# LedController2.net
KiCad netlist of a schematic drawn in EAGLE
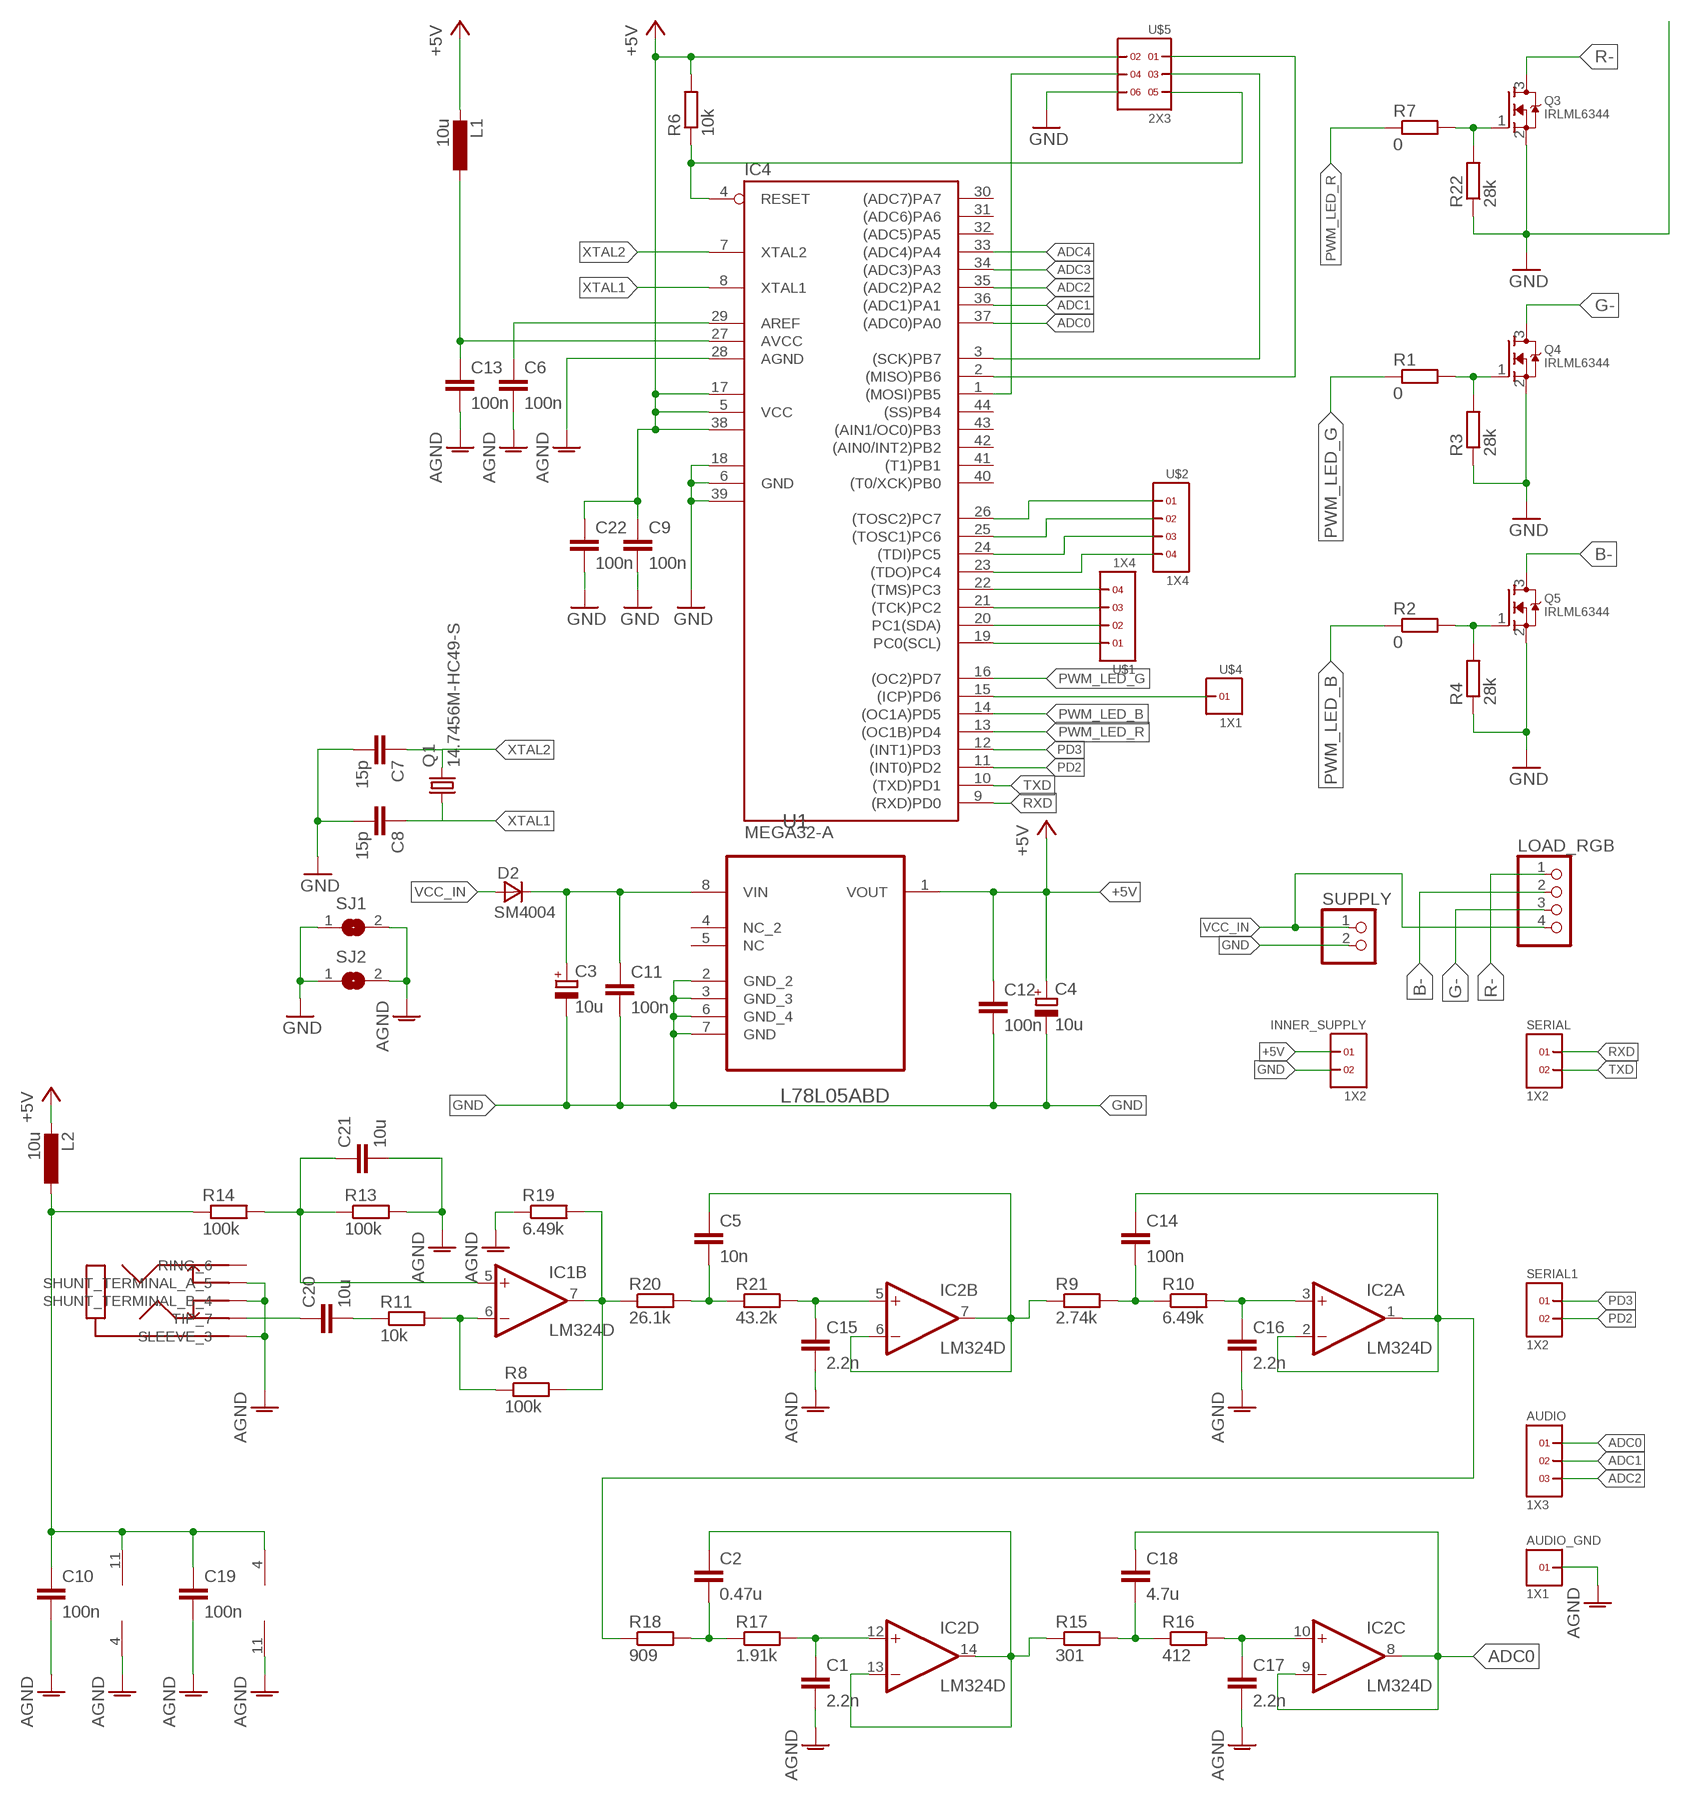
[diagram p0: schematic, sheet 1]

(export (version "E")
  (design (tool "Eeschema 10.0.6"))
  (components
    (comp (ref "AUDIO")
      (value "1X3")
      (footprint "eagle-import:1X3")
      (libsource (lib "eagle-import") (part "1X3"))
    )
    (comp (ref "AUDIO_GND")
      (value "1X1")
      (footprint "eagle-import:1X1")
      (libsource (lib "eagle-import") (part "1X1"))
    )
    (comp (ref "C1")
      (value "2.2n")
      (footprint "eagle-import:C0805")
      (libsource (lib "eagle-import") (part "C-EUC0805"))
    )
    (comp (ref "C2")
      (value "0.47u")
      (footprint "eagle-import:C0805")
      (libsource (lib "eagle-import") (part "C-EUC0805"))
    )
    (comp (ref "C3")
      (value "10u")
      (footprint "eagle-import:SMC_C")
      (libsource (lib "eagle-import") (part "CPOL-EUSMCC"))
    )
    (comp (ref "C4")
      (value "10u")
      (footprint "eagle-import:SMC_C")
      (libsource (lib "eagle-import") (part "CPOL-EUSMCC"))
    )
    (comp (ref "C5")
      (value "10n")
      (footprint "eagle-import:C0805")
      (libsource (lib "eagle-import") (part "C-EUC0805"))
    )
    (comp (ref "C6")
      (value "100n")
      (footprint "eagle-import:C0805")
      (libsource (lib "eagle-import") (part "C-EUC0805"))
    )
    (comp (ref "C7")
      (value "15p")
      (footprint "eagle-import:C0805")
      (libsource (lib "eagle-import") (part "C-EUC0805"))
    )
    (comp (ref "C8")
      (value "15p")
      (footprint "eagle-import:C0805")
      (libsource (lib "eagle-import") (part "C-EUC0805"))
    )
    (comp (ref "C9")
      (value "100n")
      (footprint "eagle-import:C0805")
      (libsource (lib "eagle-import") (part "C-EUC0805"))
    )
    (comp (ref "C10")
      (value "100n")
      (footprint "eagle-import:C0805")
      (libsource (lib "eagle-import") (part "C-EUC0805"))
    )
    (comp (ref "C11")
      (value "100n")
      (footprint "eagle-import:C0805")
      (libsource (lib "eagle-import") (part "C-EUC0805"))
    )
    (comp (ref "C12")
      (value "100n")
      (footprint "eagle-import:C0805")
      (libsource (lib "eagle-import") (part "C-EUC0805"))
    )
    (comp (ref "C13")
      (value "100n")
      (footprint "eagle-import:C0805")
      (libsource (lib "eagle-import") (part "C-EUC0805"))
    )
    (comp (ref "C14")
      (value "100n")
      (footprint "eagle-import:C0805")
      (libsource (lib "eagle-import") (part "C-EUC0805"))
    )
    (comp (ref "C15")
      (value "2.2n")
      (footprint "eagle-import:C0805")
      (libsource (lib "eagle-import") (part "C-EUC0805"))
    )
    (comp (ref "C16")
      (value "2.2n")
      (footprint "eagle-import:C0805")
      (libsource (lib "eagle-import") (part "C-EUC0805"))
    )
    (comp (ref "C17")
      (value "2.2n")
      (footprint "eagle-import:C0805")
      (libsource (lib "eagle-import") (part "C-EUC0805"))
    )
    (comp (ref "C18")
      (value "4.7u")
      (footprint "eagle-import:C0805")
      (libsource (lib "eagle-import") (part "C-EUC0805"))
    )
    (comp (ref "C19")
      (value "100n")
      (footprint "eagle-import:C0805")
      (libsource (lib "eagle-import") (part "C-EUC0805"))
    )
    (comp (ref "C20")
      (value "10u")
      (footprint "eagle-import:C0805")
      (libsource (lib "eagle-import") (part "C-EUC0805"))
    )
    (comp (ref "C21")
      (value "10u")
      (footprint "eagle-import:C0805")
      (libsource (lib "eagle-import") (part "C-EUC0805"))
    )
    (comp (ref "C22")
      (value "100n")
      (footprint "eagle-import:C0805")
      (libsource (lib "eagle-import") (part "C-EUC0805"))
    )
    (comp (ref "D2")
      (value "SM4004")
      (footprint "eagle-import:MELF-MLL41")
      (libsource (lib "eagle-import") (part "SM4004"))
    )
    (comp (ref "IC1")
      (value "LM324D")
      (footprint "eagle-import:SO14")
      (libsource (lib "eagle-import") (part "LM324D"))
    )
    (comp (ref "IC2")
      (value "LM324D")
      (footprint "eagle-import:SO14")
      (libsource (lib "eagle-import") (part "LM324D"))
    )
    (comp (ref "IC4")
      (value "MEGA32-A")
      (footprint "eagle-import:TQFP44")
      (libsource (lib "eagle-import") (part "MEGA32-A"))
    )
    (comp (ref "INNER_SUPPLY")
      (value "1X2")
      (footprint "eagle-import:1X2")
      (libsource (lib "eagle-import") (part "1X2"))
    )
    (comp (ref "L1")
      (value "10u")
      (footprint "eagle-import:L1812")
      (libsource (lib "eagle-import") (part "L-EUL1812"))
    )
    (comp (ref "L2")
      (value "10u")
      (footprint "eagle-import:L1812")
      (libsource (lib "eagle-import") (part "L-EUL1812"))
    )
    (comp (ref "LOAD_RGB")
      (value "PINHD-1X4/90")
      (footprint "eagle-import:1X04_90")
      (libsource (lib "eagle-import") (part "PINHD-1X4/90"))
    )
    (comp (ref "Q1")
      (value "14.7456M-HC49-S")
      (footprint "eagle-import:HC49_S")
      (libsource (lib "eagle-import") (part "CRYSTALHC49S"))
    )
    (comp (ref "Q3")
      (value "IRLML6344")
      (footprint "eagle-import:SOT23")
      (libsource (lib "eagle-import") (part "MOSFET-NREFLOW"))
    )
    (comp (ref "Q4")
      (value "IRLML6344")
      (footprint "eagle-import:SOT23")
      (libsource (lib "eagle-import") (part "MOSFET-NREFLOW"))
    )
    (comp (ref "Q5")
      (value "IRLML6344")
      (footprint "eagle-import:SOT23")
      (libsource (lib "eagle-import") (part "MOSFET-NREFLOW"))
    )
    (comp (ref "R1")
      (value "0")
      (footprint "eagle-import:R0805")
      (libsource (lib "eagle-import") (part "R-EU_R0805"))
    )
    (comp (ref "R2")
      (value "0")
      (footprint "eagle-import:R0805")
      (libsource (lib "eagle-import") (part "R-EU_R0805"))
    )
    (comp (ref "R3")
      (value "28k")
      (footprint "eagle-import:R0805")
      (libsource (lib "eagle-import") (part "R-EU_R0805"))
    )
    (comp (ref "R4")
      (value "28k")
      (footprint "eagle-import:R0805")
      (libsource (lib "eagle-import") (part "R-EU_R0805"))
    )
    (comp (ref "R6")
      (value "10k")
      (footprint "eagle-import:R0805")
      (libsource (lib "eagle-import") (part "R-EU_R0805"))
    )
    (comp (ref "R7")
      (value "0")
      (footprint "eagle-import:R0805")
      (libsource (lib "eagle-import") (part "R-EU_R0805"))
    )
    (comp (ref "R8")
      (value "100k")
      (footprint "eagle-import:R0805")
      (libsource (lib "eagle-import") (part "R-EU_R0805"))
    )
    (comp (ref "R9")
      (value "2.74k")
      (footprint "eagle-import:R0805")
      (libsource (lib "eagle-import") (part "R-EU_R0805"))
    )
    (comp (ref "R10")
      (value "6.49k")
      (footprint "eagle-import:R0805")
      (libsource (lib "eagle-import") (part "R-EU_R0805"))
    )
    (comp (ref "R11")
      (value "10k")
      (footprint "eagle-import:R0805")
      (libsource (lib "eagle-import") (part "R-EU_R0805"))
    )
    (comp (ref "R13")
      (value "100k")
      (footprint "eagle-import:R0805")
      (libsource (lib "eagle-import") (part "R-EU_R0805"))
    )
    (comp (ref "R14")
      (value "100k")
      (footprint "eagle-import:R0805")
      (libsource (lib "eagle-import") (part "R-EU_R0805"))
    )
    (comp (ref "R15")
      (value "301")
      (footprint "eagle-import:R0805")
      (libsource (lib "eagle-import") (part "R-EU_R0805"))
    )
    (comp (ref "R16")
      (value "412")
      (footprint "eagle-import:R0805")
      (libsource (lib "eagle-import") (part "R-EU_R0805"))
    )
    (comp (ref "R17")
      (value "1.91k")
      (footprint "eagle-import:R0805")
      (libsource (lib "eagle-import") (part "R-EU_R0805"))
    )
    (comp (ref "R18")
      (value "909")
      (footprint "eagle-import:R0805")
      (libsource (lib "eagle-import") (part "R-EU_R0805"))
    )
    (comp (ref "R19")
      (value "6.49k")
      (footprint "eagle-import:R0805")
      (libsource (lib "eagle-import") (part "R-EU_R0805"))
    )
    (comp (ref "R20")
      (value "26.1k")
      (footprint "eagle-import:R0805")
      (libsource (lib "eagle-import") (part "R-EU_R0805"))
    )
    (comp (ref "R21")
      (value "43.2k")
      (footprint "eagle-import:R0805")
      (libsource (lib "eagle-import") (part "R-EU_R0805"))
    )
    (comp (ref "R22")
      (value "28k")
      (footprint "eagle-import:R0805")
      (libsource (lib "eagle-import") (part "R-EU_R0805"))
    )
    (comp (ref "SERIAL")
      (value "1X2")
      (footprint "eagle-import:1X2")
      (libsource (lib "eagle-import") (part "1X2"))
    )
    (comp (ref "SERIAL1")
      (value "1X2")
      (footprint "eagle-import:1X2")
      (libsource (lib "eagle-import") (part "1X2"))
    )
    (comp (ref "SJ1") (value "SJ") (footprint "eagle-import:SJ") (libsource (lib "eagle-import") (part "SJ")))
    (comp (ref "SJ2") (value "SJ") (footprint "eagle-import:SJ") (libsource (lib "eagle-import") (part "SJ")))
    (comp (ref "SUPPLY")
      (value "PINHD-1X2/90")
      (footprint "eagle-import:1X02_90")
      (libsource (lib "eagle-import") (part "PINHD-1X2/90"))
    )
    (comp (ref "U$1")
      (value "1X4")
      (footprint "eagle-import:1X4")
      (libsource (lib "eagle-import") (part "1X4"))
    )
    (comp (ref "U$2")
      (value "1X4")
      (footprint "eagle-import:1X4")
      (libsource (lib "eagle-import") (part "1X4"))
    )
    (comp (ref "U$4")
      (value "1X1")
      (footprint "eagle-import:1X1")
      (libsource (lib "eagle-import") (part "1X1"))
    )
    (comp (ref "U$5")
      (value "2X3")
      (footprint "eagle-import:2X3")
      (libsource (lib "eagle-import") (part "2X3"))
    )
    (comp (ref "U$6")
      (value "JACK35")
      (footprint "eagle-import:JACK35")
      (libsource (lib "eagle-import") (part "JACK35"))
    )
    (comp (ref "U1")
      (value "L78L05ABD")
      (footprint "eagle-import:SOIC127P600X175-8N")
      (libsource (lib "eagle-import") (part "L78L05ABD"))
    )
  )
  (nets
    (net (code "1") (name "+5V") (class "Default")
      (node (ref "C12") (pin "1") (pinfunction "1_1") (pintype "passive"))
      (node (ref "C22") (pin "1") (pinfunction "1_1") (pintype "passive"))
      (node (ref "C4") (pin "+") (pinfunction "+_+") (pintype "passive"))
      (node (ref "C9") (pin "1") (pinfunction "1_1") (pintype "passive"))
      (node (ref "IC4") (pin "17") (pinfunction "VCC1_17") (pintype "power_in"))
      (node (ref "IC4") (pin "38") (pinfunction "VCC2_38") (pintype "power_in"))
      (node (ref "IC4") (pin "5") (pinfunction "VCC_5") (pintype "power_in"))
      (node (ref "INNER_SUPPLY") (pin "1") (pinfunction "1_1") (pintype "bidirectional"))
      (node (ref "L1") (pin "2") (pinfunction "2_2") (pintype "passive"))
      (node (ref "L2") (pin "2") (pinfunction "2_2") (pintype "passive"))
      (node (ref "R6") (pin "2") (pinfunction "2_2") (pintype "passive"))
      (node (ref "U$5") (pin "2") (pinfunction "2_2") (pintype "bidirectional"))
      (node (ref "U1") (pin "1") (pinfunction "VOUT_1") (pintype "output"))
    )
    (net (code "2") (name "ADC0") (class "Default")
      (node (ref "AUDIO") (pin "1") (pinfunction "1_1") (pintype "bidirectional"))
      (node (ref "C18") (pin "1") (pinfunction "1_1") (pintype "passive"))
      (node (ref "IC2") (pin "8") (pinfunction "OUT_8") (pintype "output"))
      (node (ref "IC2") (pin "9") (pinfunction "-IN_9") (pintype "input"))
      (node (ref "IC4") (pin "37") (pinfunction "(ADC0)PA0_37") (pintype "bidirectional"))
    )
    (net (code "3") (name "ADC1") (class "Default")
      (node (ref "AUDIO") (pin "2") (pinfunction "2_2") (pintype "bidirectional"))
      (node (ref "IC4") (pin "36") (pinfunction "(ADC1)PA1_36") (pintype "bidirectional"))
    )
    (net (code "4") (name "ADC2") (class "Default")
      (node (ref "AUDIO") (pin "3") (pinfunction "3_3") (pintype "bidirectional"))
      (node (ref "IC4") (pin "35") (pinfunction "(ADC2)PA2_35") (pintype "bidirectional"))
    )
    (net (code "5") (name "ADC3") (class "Default")
      (node (ref "IC4") (pin "34") (pinfunction "(ADC3)PA3_34") (pintype "bidirectional"))
    )
    (net (code "6") (name "ADC4") (class "Default")
      (node (ref "IC4") (pin "33") (pinfunction "(ADC4)PA4_33") (pintype "bidirectional"))
    )
    (net (code "7") (name "AGND") (class "Default")
      (node (ref "AUDIO_GND") (pin "1") (pinfunction "1_1") (pintype "bidirectional"))
      (node (ref "C1") (pin "2") (pinfunction "2_2") (pintype "passive"))
      (node (ref "C10") (pin "2") (pinfunction "2_2") (pintype "passive"))
      (node (ref "C13") (pin "2") (pinfunction "2_2") (pintype "passive"))
      (node (ref "C15") (pin "2") (pinfunction "2_2") (pintype "passive"))
      (node (ref "C16") (pin "2") (pinfunction "2_2") (pintype "passive"))
      (node (ref "C17") (pin "2") (pinfunction "2_2") (pintype "passive"))
      (node (ref "C19") (pin "2") (pinfunction "2_2") (pintype "passive"))
      (node (ref "C21") (pin "2") (pinfunction "2_2") (pintype "passive"))
      (node (ref "C6") (pin "2") (pinfunction "2_2") (pintype "passive"))
      (node (ref "IC1") (pin "11") (pinfunction "V-_11") (pintype "power_in"))
      (node (ref "IC2") (pin "4") (pinfunction "V+_4") (pintype "power_in"))
      (node (ref "IC4") (pin "28") (pinfunction "AGND_28") (pintype "power_in"))
      (node (ref "R13") (pin "2") (pinfunction "2_2") (pintype "passive"))
      (node (ref "R19") (pin "1") (pinfunction "1_1") (pintype "passive"))
      (node (ref "SJ1") (pin "2") (pinfunction "2_2") (pintype "passive"))
      (node (ref "SJ2") (pin "2") (pinfunction "2_2") (pintype "passive"))
      (node (ref "U$6") (pin "SHUNT_TERMINAL_A_5") (pinfunction "SHUNT_TERMINAL_A_5_SHUNT_TERMINAL_A_5") (pintype "bidirectional"))
      (node (ref "U$6") (pin "SHUNT_TERMINAL_B_4") (pinfunction "SHUNT_TERMINAL_B_4_SHUNT_TERMINAL_B_4") (pintype "bidirectional"))
      (node (ref "U$6") (pin "SLEEVE_3") (pinfunction "SLEEVE_3_SLEEVE_3") (pintype "bidirectional"))
    )
    (net (code "8") (name "B-") (class "Default")
      (node (ref "LOAD_RGB") (pin "2") (pinfunction "2_2") (pintype "passive"))
      (node (ref "Q5") (pin "3") (pinfunction "D_3") (pintype "bidirectional"))
    )
    (net (code "9") (name "G-") (class "Default")
      (node (ref "LOAD_RGB") (pin "3") (pinfunction "3_3") (pintype "passive"))
      (node (ref "Q4") (pin "3") (pinfunction "D_3") (pintype "bidirectional"))
    )
    (net (code "10") (name "GND") (class "Default")
      (node (ref "C11") (pin "2") (pinfunction "2_2") (pintype "passive"))
      (node (ref "C12") (pin "2") (pinfunction "2_2") (pintype "passive"))
      (node (ref "C22") (pin "2") (pinfunction "2_2") (pintype "passive"))
      (node (ref "C3") (pin "-") (pinfunction "-_-") (pintype "passive"))
      (node (ref "C4") (pin "-") (pinfunction "-_-") (pintype "passive"))
      (node (ref "C7") (pin "2") (pinfunction "2_2") (pintype "passive"))
      (node (ref "C8") (pin "2") (pinfunction "2_2") (pintype "passive"))
      (node (ref "C9") (pin "2") (pinfunction "2_2") (pintype "passive"))
      (node (ref "IC4") (pin "18") (pinfunction "GND1_18") (pintype "power_in"))
      (node (ref "IC4") (pin "39") (pinfunction "GND2_39") (pintype "power_in"))
      (node (ref "IC4") (pin "6") (pinfunction "GND_6") (pintype "power_in"))
      (node (ref "INNER_SUPPLY") (pin "2") (pinfunction "2_2") (pintype "bidirectional"))
      (node (ref "Q3") (pin "2") (pinfunction "S_2") (pintype "bidirectional"))
      (node (ref "Q4") (pin "2") (pinfunction "S_2") (pintype "bidirectional"))
      (node (ref "Q5") (pin "2") (pinfunction "S_2") (pintype "bidirectional"))
      (node (ref "R22") (pin "1") (pinfunction "1_1") (pintype "passive"))
      (node (ref "R3") (pin "1") (pinfunction "1_1") (pintype "passive"))
      (node (ref "R4") (pin "1") (pinfunction "1_1") (pintype "passive"))
      (node (ref "SJ1") (pin "1") (pinfunction "1_1") (pintype "passive"))
      (node (ref "SJ2") (pin "1") (pinfunction "1_1") (pintype "passive"))
      (node (ref "SUPPLY") (pin "2") (pinfunction "2_2") (pintype "passive"))
      (node (ref "U$5") (pin "6") (pinfunction "6_6") (pintype "bidirectional"))
      (node (ref "U1") (pin "2") (pinfunction "GND_2_2") (pintype "passive"))
      (node (ref "U1") (pin "3") (pinfunction "GND_3_3") (pintype "passive"))
      (node (ref "U1") (pin "6") (pinfunction "GND_4_6") (pintype "passive"))
      (node (ref "U1") (pin "7") (pinfunction "GND_7") (pintype "passive"))
    )
    (net (code "11") (name "Net-(C2-Pad2)") (class "Default")
      (node (ref "C2") (pin "2") (pinfunction "2_2") (pintype "passive"))
      (node (ref "R17") (pin "1") (pinfunction "1_1") (pintype "passive"))
      (node (ref "R18") (pin "2") (pinfunction "2_2") (pintype "passive"))
    )
    (net (code "12") (name "Net-(C5-Pad2)") (class "Default")
      (node (ref "C5") (pin "2") (pinfunction "2_2") (pintype "passive"))
      (node (ref "R20") (pin "2") (pinfunction "2_2") (pintype "passive"))
      (node (ref "R21") (pin "1") (pinfunction "1_1") (pintype "passive"))
    )
    (net (code "13") (name "Net-(C14-Pad2)") (class "Default")
      (node (ref "C14") (pin "2") (pinfunction "2_2") (pintype "passive"))
      (node (ref "R10") (pin "1") (pinfunction "1_1") (pintype "passive"))
      (node (ref "R9") (pin "2") (pinfunction "2_2") (pintype "passive"))
    )
    (net (code "14") (name "Net-(C18-Pad2)") (class "Default")
      (node (ref "C18") (pin "2") (pinfunction "2_2") (pintype "passive"))
      (node (ref "R15") (pin "2") (pinfunction "2_2") (pintype "passive"))
      (node (ref "R16") (pin "1") (pinfunction "1_1") (pintype "passive"))
    )
    (net (code "15") (name "Net-(C20-Pad1)") (class "Default")
      (node (ref "C20") (pin "1") (pinfunction "1_1") (pintype "passive"))
      (node (ref "U$6") (pin "TIP_7") (pinfunction "TIP_7_TIP_7") (pintype "bidirectional"))
    )
    (net (code "16") (name "Net-(C20-Pad2)") (class "Default")
      (node (ref "C20") (pin "2") (pinfunction "2_2") (pintype "passive"))
      (node (ref "R11") (pin "1") (pinfunction "1_1") (pintype "passive"))
    )
    (net (code "17") (name "Net-(IC1B-+IN)") (class "Default")
      (node (ref "C21") (pin "1") (pinfunction "1_1") (pintype "passive"))
      (node (ref "IC1") (pin "5") (pinfunction "+IN_5") (pintype "input"))
      (node (ref "R13") (pin "1") (pinfunction "1_1") (pintype "passive"))
      (node (ref "R14") (pin "2") (pinfunction "2_2") (pintype "passive"))
    )
    (net (code "18") (name "Net-(IC1B--IN)") (class "Default")
      (node (ref "IC1") (pin "6") (pinfunction "-IN_6") (pintype "input"))
      (node (ref "R11") (pin "2") (pinfunction "2_2") (pintype "passive"))
      (node (ref "R8") (pin "1") (pinfunction "1_1") (pintype "passive"))
    )
    (net (code "19") (name "Net-(IC1B-OUT)") (class "Default")
      (node (ref "IC1") (pin "7") (pinfunction "OUT_7") (pintype "output"))
      (node (ref "R19") (pin "2") (pinfunction "2_2") (pintype "passive"))
      (node (ref "R20") (pin "1") (pinfunction "1_1") (pintype "passive"))
      (node (ref "R8") (pin "2") (pinfunction "2_2") (pintype "passive"))
    )
    (net (code "20") (name "Net-(IC1E-V+)") (class "Default")
      (node (ref "C10") (pin "1") (pinfunction "1_1") (pintype "passive"))
      (node (ref "C19") (pin "1") (pinfunction "1_1") (pintype "passive"))
      (node (ref "IC1") (pin "4") (pinfunction "V+_4") (pintype "power_in"))
      (node (ref "IC2") (pin "11") (pinfunction "V-_11") (pintype "power_in"))
      (node (ref "L2") (pin "1") (pinfunction "1_1") (pintype "passive"))
      (node (ref "R14") (pin "1") (pinfunction "1_1") (pintype "passive"))
    )
    (net (code "21") (name "Net-(IC2A-+IN)") (class "Default")
      (node (ref "C16") (pin "1") (pinfunction "1_1") (pintype "passive"))
      (node (ref "IC2") (pin "3") (pinfunction "+IN_3") (pintype "input"))
      (node (ref "R10") (pin "2") (pinfunction "2_2") (pintype "passive"))
    )
    (net (code "22") (name "Net-(IC2A--IN)") (class "Default")
      (node (ref "C14") (pin "1") (pinfunction "1_1") (pintype "passive"))
      (node (ref "IC2") (pin "1") (pinfunction "OUT_1") (pintype "output"))
      (node (ref "IC2") (pin "2") (pinfunction "-IN_2") (pintype "input"))
      (node (ref "R18") (pin "1") (pinfunction "1_1") (pintype "passive"))
    )
    (net (code "23") (name "Net-(IC2B-+IN)") (class "Default")
      (node (ref "C15") (pin "1") (pinfunction "1_1") (pintype "passive"))
      (node (ref "IC2") (pin "5") (pinfunction "+IN_5") (pintype "input"))
      (node (ref "R21") (pin "2") (pinfunction "2_2") (pintype "passive"))
    )
    (net (code "24") (name "Net-(IC2B--IN)") (class "Default")
      (node (ref "C5") (pin "1") (pinfunction "1_1") (pintype "passive"))
      (node (ref "IC2") (pin "6") (pinfunction "-IN_6") (pintype "input"))
      (node (ref "IC2") (pin "7") (pinfunction "OUT_7") (pintype "output"))
      (node (ref "R9") (pin "1") (pinfunction "1_1") (pintype "passive"))
    )
    (net (code "25") (name "Net-(IC2C-+IN)") (class "Default")
      (node (ref "C17") (pin "1") (pinfunction "1_1") (pintype "passive"))
      (node (ref "IC2") (pin "10") (pinfunction "+IN_10") (pintype "input"))
      (node (ref "R16") (pin "2") (pinfunction "2_2") (pintype "passive"))
    )
    (net (code "26") (name "Net-(IC2D-+IN)") (class "Default")
      (node (ref "C1") (pin "1") (pinfunction "1_1") (pintype "passive"))
      (node (ref "IC2") (pin "12") (pinfunction "+IN_12") (pintype "input"))
      (node (ref "R17") (pin "2") (pinfunction "2_2") (pintype "passive"))
    )
    (net (code "27") (name "Net-(IC2D--IN)") (class "Default")
      (node (ref "C2") (pin "1") (pinfunction "1_1") (pintype "passive"))
      (node (ref "IC2") (pin "13") (pinfunction "-IN_13") (pintype "input"))
      (node (ref "IC2") (pin "14") (pinfunction "OUT_14") (pintype "output"))
      (node (ref "R15") (pin "1") (pinfunction "1_1") (pintype "passive"))
    )
    (net (code "28") (name "Net-(IC4-(ICP)PD6)") (class "Default")
      (node (ref "IC4") (pin "15") (pinfunction "(ICP)PD6_15") (pintype "bidirectional"))
      (node (ref "U$4") (pin "1") (pinfunction "1_1") (pintype "bidirectional"))
    )
    (net (code "29") (name "Net-(IC4-(MISO)PB6)") (class "Default")
      (node (ref "IC4") (pin "2") (pinfunction "(MISO)PB6_2") (pintype "bidirectional"))
      (node (ref "U$5") (pin "1") (pinfunction "1_1") (pintype "bidirectional"))
    )
    (net (code "30") (name "Net-(IC4-(MOSI)PB5)") (class "Default")
      (node (ref "IC4") (pin "1") (pinfunction "(MOSI)PB5_1") (pintype "bidirectional"))
      (node (ref "U$5") (pin "4") (pinfunction "4_4") (pintype "bidirectional"))
    )
    (net (code "31") (name "Net-(IC4-(SCK)PB7)") (class "Default")
      (node (ref "IC4") (pin "3") (pinfunction "(SCK)PB7_3") (pintype "bidirectional"))
      (node (ref "U$5") (pin "3") (pinfunction "3_3") (pintype "bidirectional"))
    )
    (net (code "32") (name "Net-(IC4-(TCK)PC2)") (class "Default")
      (node (ref "IC4") (pin "21") (pinfunction "(TCK)PC2_21") (pintype "bidirectional"))
      (node (ref "U$1") (pin "3") (pinfunction "3_3") (pintype "bidirectional"))
    )
    (net (code "33") (name "Net-(IC4-(TDI)PC5)") (class "Default")
      (node (ref "IC4") (pin "24") (pinfunction "(TDI)PC5_24") (pintype "bidirectional"))
      (node (ref "U$2") (pin "3") (pinfunction "3_3") (pintype "bidirectional"))
    )
    (net (code "34") (name "Net-(IC4-(TDO)PC4)") (class "Default")
      (node (ref "IC4") (pin "23") (pinfunction "(TDO)PC4_23") (pintype "bidirectional"))
      (node (ref "U$2") (pin "4") (pinfunction "4_4") (pintype "bidirectional"))
    )
    (net (code "35") (name "Net-(IC4-(TMS)PC3)") (class "Default")
      (node (ref "IC4") (pin "22") (pinfunction "(TMS)PC3_22") (pintype "bidirectional"))
      (node (ref "U$1") (pin "4") (pinfunction "4_4") (pintype "bidirectional"))
    )
    (net (code "36") (name "Net-(IC4-(TOSC1)PC6)") (class "Default")
      (node (ref "IC4") (pin "25") (pinfunction "(TOSC1)PC6_25") (pintype "bidirectional"))
      (node (ref "U$2") (pin "2") (pinfunction "2_2") (pintype "bidirectional"))
    )
    (net (code "37") (name "Net-(IC4-(TOSC2)PC7)") (class "Default")
      (node (ref "IC4") (pin "26") (pinfunction "(TOSC2)PC7_26") (pintype "bidirectional"))
      (node (ref "U$2") (pin "1") (pinfunction "1_1") (pintype "bidirectional"))
    )
    (net (code "38") (name "Net-(IC4-AREF)") (class "Default")
      (node (ref "C6") (pin "1") (pinfunction "1_1") (pintype "passive"))
      (node (ref "IC4") (pin "29") (pinfunction "AREF_29") (pintype "power_in"))
    )
    (net (code "39") (name "Net-(IC4-AVCC)") (class "Default")
      (node (ref "C13") (pin "1") (pinfunction "1_1") (pintype "passive"))
      (node (ref "IC4") (pin "27") (pinfunction "AVCC_27") (pintype "power_in"))
      (node (ref "L1") (pin "1") (pinfunction "1_1") (pintype "passive"))
    )
    (net (code "40") (name "Net-(IC4-PC0(SCL))") (class "Default")
      (node (ref "IC4") (pin "19") (pinfunction "PC0(SCL)_19") (pintype "bidirectional"))
      (node (ref "U$1") (pin "1") (pinfunction "1_1") (pintype "bidirectional"))
    )
    (net (code "41") (name "Net-(IC4-PC1(SDA))") (class "Default")
      (node (ref "IC4") (pin "20") (pinfunction "PC1(SDA)_20") (pintype "bidirectional"))
      (node (ref "U$1") (pin "2") (pinfunction "2_2") (pintype "bidirectional"))
    )
    (net (code "42") (name "Net-(IC4-RESET)") (class "Default")
      (node (ref "IC4") (pin "4") (pinfunction "RESET_4") (pintype "input"))
      (node (ref "R6") (pin "1") (pinfunction "1_1") (pintype "passive"))
      (node (ref "U$5") (pin "5") (pinfunction "5_5") (pintype "bidirectional"))
    )
    (net (code "43") (name "Net-(Q3-G)") (class "Default")
      (node (ref "Q3") (pin "1") (pinfunction "G_1") (pintype "bidirectional"))
      (node (ref "R22") (pin "2") (pinfunction "2_2") (pintype "passive"))
      (node (ref "R7") (pin "2") (pinfunction "2_2") (pintype "passive"))
    )
    (net (code "44") (name "Net-(Q4-G)") (class "Default")
      (node (ref "Q4") (pin "1") (pinfunction "G_1") (pintype "bidirectional"))
      (node (ref "R1") (pin "2") (pinfunction "2_2") (pintype "passive"))
      (node (ref "R3") (pin "2") (pinfunction "2_2") (pintype "passive"))
    )
    (net (code "45") (name "Net-(Q5-G)") (class "Default")
      (node (ref "Q5") (pin "1") (pinfunction "G_1") (pintype "bidirectional"))
      (node (ref "R2") (pin "2") (pinfunction "2_2") (pintype "passive"))
      (node (ref "R4") (pin "2") (pinfunction "2_2") (pintype "passive"))
    )
    (net (code "46") (name "Net-(U1-VIN)") (class "Default")
      (node (ref "C11") (pin "1") (pinfunction "1_1") (pintype "passive"))
      (node (ref "C3") (pin "+") (pinfunction "+_+") (pintype "passive"))
      (node (ref "D2") (pin "C") (pinfunction "C_C") (pintype "passive"))
      (node (ref "U1") (pin "8") (pinfunction "VIN_8") (pintype "power_in"))
    )
    (net (code "47") (name "PD2") (class "Default")
      (node (ref "IC4") (pin "11") (pinfunction "(INT0)PD2_11") (pintype "bidirectional"))
      (node (ref "SERIAL1") (pin "2") (pinfunction "2_2") (pintype "bidirectional"))
    )
    (net (code "48") (name "PD3") (class "Default")
      (node (ref "IC4") (pin "12") (pinfunction "(INT1)PD3_12") (pintype "bidirectional"))
      (node (ref "SERIAL1") (pin "1") (pinfunction "1_1") (pintype "bidirectional"))
    )
    (net (code "49") (name "PWM_LED_B") (class "Default")
      (node (ref "IC4") (pin "14") (pinfunction "(OC1A)PD5_14") (pintype "bidirectional"))
      (node (ref "R2") (pin "1") (pinfunction "1_1") (pintype "passive"))
    )
    (net (code "50") (name "PWM_LED_G") (class "Default")
      (node (ref "IC4") (pin "16") (pinfunction "(OC2)PD7_16") (pintype "bidirectional"))
      (node (ref "R1") (pin "1") (pinfunction "1_1") (pintype "passive"))
    )
    (net (code "51") (name "PWM_LED_R") (class "Default")
      (node (ref "IC4") (pin "13") (pinfunction "(OC1B)PD4_13") (pintype "bidirectional"))
      (node (ref "R7") (pin "1") (pinfunction "1_1") (pintype "passive"))
    )
    (net (code "52") (name "R-") (class "Default")
      (node (ref "LOAD_RGB") (pin "1") (pinfunction "1_1") (pintype "passive"))
      (node (ref "Q3") (pin "3") (pinfunction "D_3") (pintype "bidirectional"))
    )
    (net (code "53") (name "RXD") (class "Default")
      (node (ref "IC4") (pin "9") (pinfunction "(RXD)PD0_9") (pintype "bidirectional"))
      (node (ref "SERIAL") (pin "1") (pinfunction "1_1") (pintype "bidirectional"))
    )
    (net (code "54") (name "TXD") (class "Default")
      (node (ref "IC4") (pin "10") (pinfunction "(TXD)PD1_10") (pintype "bidirectional"))
      (node (ref "SERIAL") (pin "2") (pinfunction "2_2") (pintype "bidirectional"))
    )
    (net (code "55") (name "VCC_IN") (class "Default")
      (node (ref "D2") (pin "A") (pinfunction "A_A") (pintype "passive"))
      (node (ref "LOAD_RGB") (pin "4") (pinfunction "4_4") (pintype "passive"))
      (node (ref "SUPPLY") (pin "1") (pinfunction "1_1") (pintype "passive"))
    )
    (net (code "56") (name "XTAL1") (class "Default")
      (node (ref "C8") (pin "1") (pinfunction "1_1") (pintype "passive"))
      (node (ref "IC4") (pin "8") (pinfunction "XTAL1_8") (pintype "bidirectional"))
      (node (ref "Q1") (pin "1") (pinfunction "1_1") (pintype "passive"))
    )
    (net (code "57") (name "XTAL2") (class "Default")
      (node (ref "C7") (pin "1") (pinfunction "1_1") (pintype "passive"))
      (node (ref "IC4") (pin "7") (pinfunction "XTAL2_7") (pintype "bidirectional"))
      (node (ref "Q1") (pin "2") (pinfunction "2_2") (pintype "passive"))
    )
    (net (code "58") (name "unconnected-(IC4-(ADC5)PA5-Pad32)") (class "Default")
      (node (ref "IC4") (pin "32") (pinfunction "(ADC5)PA5_32") (pintype "bidirectional"))
    )
    (net (code "59") (name "unconnected-(IC4-(ADC6)PA6-Pad31)") (class "Default")
      (node (ref "IC4") (pin "31") (pinfunction "(ADC6)PA6_31") (pintype "bidirectional"))
    )
    (net (code "60") (name "unconnected-(IC4-(ADC7)PA7-Pad30)") (class "Default")
      (node (ref "IC4") (pin "30") (pinfunction "(ADC7)PA7_30") (pintype "bidirectional"))
    )
    (net (code "61") (name "unconnected-(IC4-(AIN0{slash}INT2)PB2-Pad42)") (class "Default")
      (node (ref "IC4") (pin "42") (pinfunction "(AIN0/INT2)PB2_42") (pintype "bidirectional"))
    )
    (net (code "62") (name "unconnected-(IC4-(AIN1{slash}OC0)PB3-Pad43)") (class "Default")
      (node (ref "IC4") (pin "43") (pinfunction "(AIN1/OC0)PB3_43") (pintype "bidirectional"))
    )
    (net (code "63") (name "unconnected-(IC4-(SS)PB4-Pad44)") (class "Default")
      (node (ref "IC4") (pin "44") (pinfunction "(SS)PB4_44") (pintype "bidirectional"))
    )
    (net (code "64") (name "unconnected-(IC4-(T0{slash}XCK)PB0-Pad40)") (class "Default")
      (node (ref "IC4") (pin "40") (pinfunction "(T0/XCK)PB0_40") (pintype "bidirectional"))
    )
    (net (code "65") (name "unconnected-(IC4-(T1)PB1-Pad41)") (class "Default")
      (node (ref "IC4") (pin "41") (pinfunction "(T1)PB1_41") (pintype "bidirectional"))
    )
    (net (code "66") (name "unconnected-(U$6-PadRING_6)") (class "Default")
      (node (ref "U$6") (pin "RING_6") (pinfunction "RING_6_RING_6") (pintype "bidirectional"))
    )
    (net (code "67") (name "unconnected-(U1-NC-Pad5)") (class "Default")
      (node (ref "U1") (pin "5") (pinfunction "NC_5") (pintype "no_connect"))
    )
    (net (code "68") (name "unconnected-(U1-NC_2-Pad4)") (class "Default")
      (node (ref "U1") (pin "4") (pinfunction "NC_2_4") (pintype "no_connect"))
    )
  )
)
